# Power_Pos.net
KiCad netlist of a schematic drawn in Altium Designer
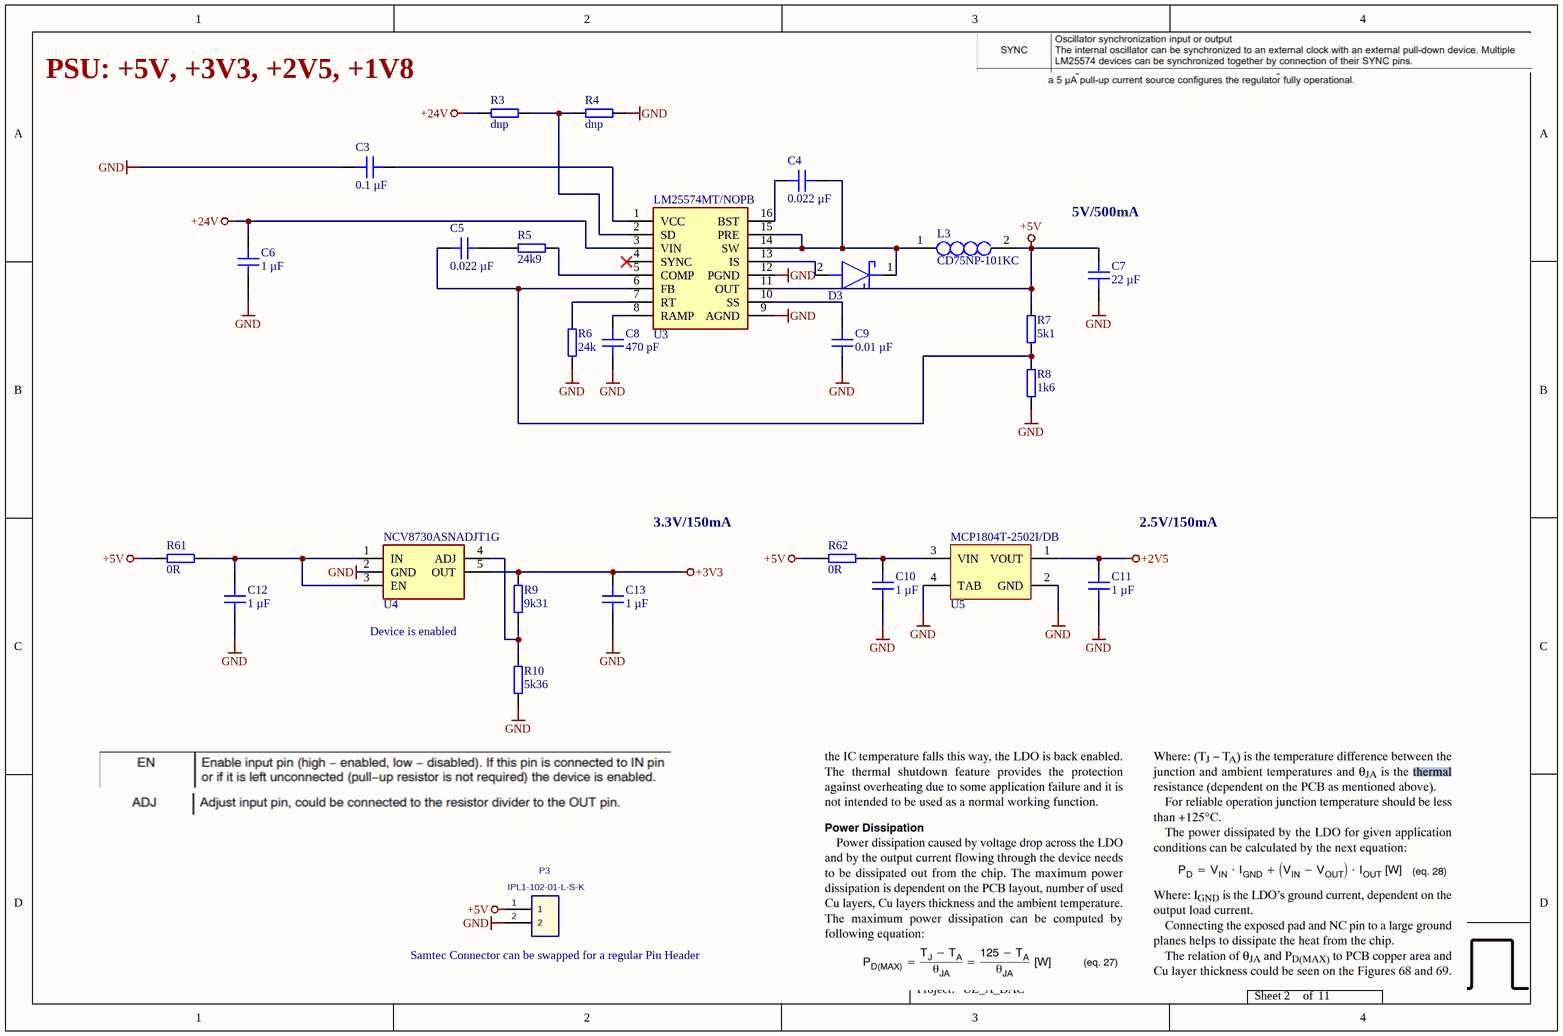
[diagram p0: Power_Pos.SchDoc]

(export (version "E")
  (design (tool "Eeschema 10.0.6"))
  (components
    (comp (ref "C3")
      (value "0.1 µF")
      (footprint "C_0603")
      (description "Capacitor 0603, 50 VDC, 0.1 µF, X7R")
      (fields
        (field (name "MANUFACTURER PART NUMBER") "C0603X104K5RAC7411")
        (field (name "MANUFACTURER") "KEMET")
        (field (name "CREATED FROM") "MGremer")
      )
      (libsource (lib "user") (part "Capacitor"))
    )
    (comp (ref "C4")
      (value "0.022 µF")
      (footprint "C_0805")
      (description "Capacitor 0805, 100 VDC, 0.022 µF, X7R")
      (fields
        (field (name "MANUFACTURER PART NUMBER") "C0805J223K1RACAUTO")
        (field (name "MANUFACTURER") "KEMET")
        (field (name "CREATED FROM") "MGremer")
      )
      (libsource (lib "user") (part "Capacitor"))
    )
    (comp (ref "C5")
      (value "0.022 µF")
      (footprint "C_0805")
      (description "Capacitor 0805, 100 VDC, 0.022 µF, X7R")
      (fields
        (field (name "MANUFACTURER PART NUMBER") "C0805J223K1RACAUTO")
        (field (name "MANUFACTURER") "KEMET")
        (field (name "CREATED FROM") "MGremer")
      )
      (libsource (lib "user") (part "Capacitor"))
    )
    (comp (ref "C6")
      (value "1 µF")
      (footprint "C_1206")
      (description "Capacitor 1206, 50 VDC, 1 µF, X7R")
      (fields
        (field (name "MANUFACTURER PART NUMBER") "C1206X105K5RECAUTO")
        (field (name "MANUFACTURER") "KEMET")
        (field (name "CREATED FROM") "MGremer")
      )
      (libsource (lib "user") (part "Capacitor"))
    )
    (comp (ref "C7")
      (value "22 µF")
      (footprint "C_0805")
      (description "Capacitor 0805, 25 VDC, 22 µF, X5R")
      (fields
        (field (name "MANUFACTURER PART NUMBER") "GRT21BR61E226ME13L")
        (field (name "MANUFACTURER") "muRata")
        (field (name "CREATED FROM") "MGremer")
      )
      (libsource (lib "user") (part "Capacitor"))
    )
    (comp (ref "C8")
      (value "470 pF")
      (footprint "C_0805")
      (description "Capacitor 0805, 50 VDC, 470 pF, X7R")
      (fields
        (field (name "MANUFACTURER PART NUMBER") "CC805KRX7R9BB471")
        (field (name "MANUFACTURER") "FH")
        (field (name "CREATED FROM") "MHlatky")
      )
      (libsource (lib "user") (part "Capacitor"))
    )
    (comp (ref "C9")
      (value "0.01 µF")
      (footprint "C_0603")
      (description "Capacitor 0603, 50 VDC, 0.01 µF, X7R")
      (fields
        (field (name "MANUFACTURER PART NUMBER") "GCJ188R71H103KA01D")
        (field (name "MANUFACTURER") "muRata")
        (field (name "CREATED FROM") "MGremer")
      )
      (libsource (lib "user") (part "Capacitor"))
    )
    (comp (ref "C10")
      (value "1 µF")
      (footprint "C_1206")
      (description "Capacitor 1206, 50 VDC, 1 µF, X7R")
      (fields
        (field (name "MANUFACTURER PART NUMBER") "C1206X105K5RECAUTO")
        (field (name "MANUFACTURER") "KEMET")
        (field (name "CREATED FROM") "MGremer")
      )
      (libsource (lib "user") (part "Capacitor"))
    )
    (comp (ref "C11")
      (value "1 µF")
      (footprint "C_1206")
      (description "Capacitor 1206, 50 VDC, 1 µF, X7R")
      (fields
        (field (name "MANUFACTURER PART NUMBER") "C1206X105K5RECAUTO")
        (field (name "MANUFACTURER") "KEMET")
        (field (name "CREATED FROM") "MGremer")
      )
      (libsource (lib "user") (part "Capacitor"))
    )
    (comp (ref "C12")
      (value "1 µF")
      (footprint "C_1206")
      (description "Capacitor 1206, 50 VDC, 1 µF, X7R")
      (fields
        (field (name "MANUFACTURER PART NUMBER") "C1206X105K5RECAUTO")
        (field (name "MANUFACTURER") "KEMET")
        (field (name "CREATED FROM") "MGremer")
      )
      (libsource (lib "user") (part "Capacitor"))
    )
    (comp (ref "C13")
      (value "1 µF")
      (footprint "C_1206")
      (description "Capacitor 1206, 50 VDC, 1 µF, X7R")
      (fields
        (field (name "MANUFACTURER PART NUMBER") "C1206X105K5RECAUTO")
        (field (name "MANUFACTURER") "KEMET")
        (field (name "CREATED FROM") "MGremer")
      )
      (libsource (lib "user") (part "Capacitor"))
    )
    (comp (ref "D3")
      (value "CDBA260-G")
      (footprint "DIOM5226X262N")
      (description "Schottky Diode, 60 V, 2 A")
      (fields
        (field (name "MANUFACTURER_PART_NUMBER") "CMSH2-60M TR13 PBFREE")
        (field (name "MANUFACTURER") "Central Semiconductor")
        (field (name "CREATED FROM") "MHlatky")
      )
      (libsource (lib "user") (part "CDBA260-G"))
    )
    (comp (ref "L3")
      (value "CD75NP-101KC")
      (footprint "784787121")
      (description "SMD Power Inductor, 100uH")
      (fields
        (field (name "MANUFACTURER_PART_NUMBER") "784787121")
        (field (name "MANUFACTURER") "Sumida")
        (field (name "CREATED FROM") "MHlatky")
      )
      (libsource (lib "user") (part "CD75NP-101KC"))
    )
    (comp (ref "P3")
      (value "IPL1-102-01-L-S-K")
      (footprint "IPL1-102-01-YYY-S-K")
      (description "2.54 mm Single Row Terminal Assembly")
      (fields (field (name "MANUFACTURER") "SAMTEC") (field (name "CREATED FROM") "MGremer"))
      (libsource (lib "user") (part "IPL1-102-XX-X-S-X"))
    )
    (comp (ref "R3")
      (value "dnp")
      (footprint "RES 0603_1608")
      (description "SMD resistor E24 series")
      (fields (field (name "CREATED FROM") "MGremer"))
      (libsource (lib "user") (part "Resistor"))
    )
    (comp (ref "R4")
      (value "dnp")
      (footprint "RES 0603_1608")
      (description "SMD resistor E24 series")
      (fields (field (name "CREATED FROM") "MGremer"))
      (libsource (lib "user") (part "Resistor"))
    )
    (comp (ref "R5")
      (value "24k9")
      (footprint "RES 0603_1608")
      (description "SMD resistor 1%")
      (fields
        (field (name "MANUFACTURER PART NUMBER") "CRCW060324K9FKEA")
        (field (name "MANUFACTURER") "Vishay")
        (field (name "CREATED FROM") "MGremer")
      )
      (libsource (lib "user") (part "Resistor"))
    )
    (comp (ref "R6")
      (value "24k")
      (footprint "RES 0603_1608")
      (description "SMD resistor E24 series")
      (fields
        (field (name "MANUFACTURER PART NUMBER") "RK73B1JTTD243J")
        (field (name "MANUFACTURER") "KOA Speer")
        (field (name "CREATED FROM") "MGremer")
      )
      (libsource (lib "user") (part "Resistor"))
    )
    (comp (ref "R7")
      (value "5k1")
      (footprint "RES 0603_1608")
      (description "SMD resistor E24 series")
      (fields
        (field (name "MANUFACTURER PART NUMBER") "RK73B1JTTDD512J")
        (field (name "MANUFACTURER") "KOA Speer")
        (field (name "CREATED FROM") "MGremer")
      )
      (libsource (lib "user") (part "Resistor"))
    )
    (comp (ref "R8")
      (value "1k6")
      (footprint "RES 0603_1608")
      (description "SMD resistor E24 series")
      (fields
        (field (name "MANUFACTURER PART NUMBER") "RK73B1JTTD162J")
        (field (name "MANUFACTURER") "KOA Speer")
        (field (name "CREATED FROM") "MGremer")
      )
      (libsource (lib "user") (part "Resistor"))
    )
    (comp (ref "R9")
      (value "9k31")
      (footprint "RES 0603_1608")
      (description "SMD resistor 1%")
      (fields
        (field (name "MANUFACTURER PART NUMBER") "ERJ3EKF9311V")
        (field (name "MANUFACTURER") "Panasonic")
        (field (name "CREATED FROM") "MGremer")
      )
      (libsource (lib "user") (part "Resistor"))
    )
    (comp (ref "R10")
      (value "5k36")
      (footprint "RES 0603_1608")
      (description "SMD resistor 1%")
      (fields
        (field (name "MANUFACTURER PART NUMBER") "AC0603FR-075K36L")
        (field (name "MANUFACTURER") "YAGEO")
        (field (name "CREATED FROM") "MGremer")
      )
      (libsource (lib "user") (part "Resistor"))
    )
    (comp (ref "R61")
      (value "0R")
      (footprint "RES 0603_1608")
      (description "SMD resistor E24 series")
      (fields
        (field (name "MANUFACTURER PART NUMBER") "RC0603JR-070RL")
        (field (name "MANUFACTURER") "YAGEO")
        (field (name "CREATED FROM") "MGremer")
      )
      (libsource (lib "user") (part "Resistor"))
    )
    (comp (ref "R62")
      (value "0R")
      (footprint "RES 0603_1608")
      (description "SMD resistor E24 series")
      (fields
        (field (name "MANUFACTURER PART NUMBER") "RC0603JR-070RL")
        (field (name "MANUFACTURER") "YAGEO")
        (field (name "CREATED FROM") "MGremer")
      )
      (libsource (lib "user") (part "Resistor"))
    )
    (comp (ref "U3")
      (value "LM25574MT/NOPB")
      (footprint "SOP65P640X120-16N")
      (description "42-V, 0.5-A Step-Down Switching Regulator")
      (fields (field (name "MANUFACTURER") "TI") (field (name "CREATED FROM") "MHlatky"))
      (libsource (lib "user") (part "LM25574MT_NOPB"))
    )
    (comp (ref "U4")
      (value "NCV8730ASNADJT1G")
      (footprint "SOT95P275X110-5N")
      (description "LDO Regulator, 150 mA, 38V, 1 A IQ, with PG")
      (fields (field (name "MANUFACTURER") "onsemi") (field (name "CREATED FROM") "MHlatky"))
      (libsource (lib "user") (part "NCV8730ASNADJT1G"))
    )
    (comp (ref "U5")
      (value "MCP1804T-2502I/DB")
      (footprint "SOT-223-DB3_N")
      (description "150 mA, 28V LDO Regulator With Shutdown")
      (fields (field (name "MANUFACTURER") "Microchip Technology") (field (name "CREATED FROM") "MHlatky"))
      (libsource (lib "user") (part "MCP1804T-2502I/DB"))
    )
  )
  (nets
    (net (code "1") (name "+2V5") (class "Default")
      (node (ref "C11") (pin "2") (pinfunction "2_2") (pintype "passive"))
      (node (ref "U5") (pin "1") (pinfunction "VOUT_1") (pintype "power_in"))
    )
    (net (code "2") (name "+3V3") (class "Default")
      (node (ref "C13") (pin "2") (pinfunction "2_2") (pintype "passive"))
      (node (ref "R9") (pin "2") (pinfunction "2_2") (pintype "passive"))
      (node (ref "U4") (pin "5") (pinfunction "OUT_5") (pintype "passive"))
    )
    (net (code "3") (name "+5V") (class "Default")
      (node (ref "C7") (pin "2") (pinfunction "2_2") (pintype "passive"))
      (node (ref "L3") (pin "2") (pinfunction "2_2") (pintype "passive"))
      (node (ref "P3") (pin "1") (pinfunction "1_1") (pintype "passive"))
      (node (ref "R61") (pin "1") (pinfunction "1_1") (pintype "passive"))
      (node (ref "R62") (pin "1") (pinfunction "1_1") (pintype "passive"))
      (node (ref "R7") (pin "2") (pinfunction "2_2") (pintype "passive"))
      (node (ref "U3") (pin "11") (pinfunction "OUT_11") (pintype "passive"))
    )
    (net (code "4") (name "+24V") (class "Default")
      (node (ref "C6") (pin "2") (pinfunction "2_2") (pintype "passive"))
      (node (ref "R3") (pin "1") (pinfunction "1_1") (pintype "passive"))
      (node (ref "U3") (pin "3") (pinfunction "VIN_3") (pintype "passive"))
    )
    (net (code "5") (name "GND") (class "Default")
      (node (ref "C10") (pin "1") (pinfunction "1_1") (pintype "passive"))
      (node (ref "C11") (pin "1") (pinfunction "1_1") (pintype "passive"))
      (node (ref "C12") (pin "1") (pinfunction "1_1") (pintype "passive"))
      (node (ref "C13") (pin "1") (pinfunction "1_1") (pintype "passive"))
      (node (ref "C3") (pin "2") (pinfunction "2_2") (pintype "passive"))
      (node (ref "C6") (pin "1") (pinfunction "1_1") (pintype "passive"))
      (node (ref "C7") (pin "1") (pinfunction "1_1") (pintype "passive"))
      (node (ref "C8") (pin "1") (pinfunction "1_1") (pintype "passive"))
      (node (ref "C9") (pin "1") (pinfunction "1_1") (pintype "passive"))
      (node (ref "P3") (pin "2") (pinfunction "2_2") (pintype "passive"))
      (node (ref "R10") (pin "1") (pinfunction "1_1") (pintype "passive"))
      (node (ref "R4") (pin "2") (pinfunction "2_2") (pintype "passive"))
      (node (ref "R6") (pin "1") (pinfunction "1_1") (pintype "passive"))
      (node (ref "R8") (pin "1") (pinfunction "1_1") (pintype "passive"))
      (node (ref "U3") (pin "12") (pinfunction "PGND_12") (pintype "passive"))
      (node (ref "U3") (pin "9") (pinfunction "AGND_9") (pintype "passive"))
      (node (ref "U4") (pin "2") (pinfunction "GND_2") (pintype "passive"))
      (node (ref "U5") (pin "2") (pinfunction "GND_2") (pintype "power_in"))
      (node (ref "U5") (pin "4") (pinfunction "TAB_4") (pintype "power_in"))
    )
    (net (code "6") (name "Net-(C5-Pad2)") (class "Default")
      (node (ref "C5") (pin "2") (pinfunction "2_2") (pintype "passive"))
      (node (ref "R5") (pin "1") (pinfunction "1_1") (pintype "passive"))
    )
    (net (code "7") (name "Net-(D3-A)") (class "Default")
      (node (ref "D3") (pin "2") (pinfunction "A_2") (pintype "passive"))
      (node (ref "U3") (pin "13") (pinfunction "IS_13") (pintype "passive"))
    )
    (net (code "8") (name "Net-(D3-K)") (class "Default")
      (node (ref "C4") (pin "2") (pinfunction "2_2") (pintype "passive"))
      (node (ref "D3") (pin "1") (pinfunction "K_1") (pintype "passive"))
      (node (ref "L3") (pin "1") (pinfunction "1_1") (pintype "passive"))
      (node (ref "U3") (pin "14") (pinfunction "SW_14") (pintype "passive"))
      (node (ref "U3") (pin "15") (pinfunction "PRE_15") (pintype "passive"))
    )
    (net (code "9") (name "Net-(U3-BST)") (class "Default")
      (node (ref "C4") (pin "1") (pinfunction "1_1") (pintype "passive"))
      (node (ref "U3") (pin "16") (pinfunction "BST_16") (pintype "passive"))
    )
    (net (code "10") (name "Net-(U3-COMP)") (class "Default")
      (node (ref "R5") (pin "2") (pinfunction "2_2") (pintype "passive"))
      (node (ref "U3") (pin "5") (pinfunction "COMP_5") (pintype "passive"))
    )
    (net (code "11") (name "Net-(U3-FB)") (class "Default")
      (node (ref "C5") (pin "1") (pinfunction "1_1") (pintype "passive"))
      (node (ref "R7") (pin "1") (pinfunction "1_1") (pintype "passive"))
      (node (ref "R8") (pin "2") (pinfunction "2_2") (pintype "passive"))
      (node (ref "U3") (pin "6") (pinfunction "FB_6") (pintype "passive"))
    )
    (net (code "12") (name "Net-(U3-RAMP)") (class "Default")
      (node (ref "C8") (pin "2") (pinfunction "2_2") (pintype "passive"))
      (node (ref "U3") (pin "8") (pinfunction "RAMP_8") (pintype "passive"))
    )
    (net (code "13") (name "Net-(U3-RT)") (class "Default")
      (node (ref "R6") (pin "2") (pinfunction "2_2") (pintype "passive"))
      (node (ref "U3") (pin "7") (pinfunction "RT_7") (pintype "passive"))
    )
    (net (code "14") (name "Net-(U3-SD)") (class "Default")
      (node (ref "R3") (pin "2") (pinfunction "2_2") (pintype "passive"))
      (node (ref "R4") (pin "1") (pinfunction "1_1") (pintype "passive"))
      (node (ref "U3") (pin "2") (pinfunction "SD_2") (pintype "passive"))
    )
    (net (code "15") (name "Net-(U3-SS)") (class "Default")
      (node (ref "C9") (pin "2") (pinfunction "2_2") (pintype "passive"))
      (node (ref "U3") (pin "10") (pinfunction "SS_10") (pintype "passive"))
    )
    (net (code "16") (name "Net-(U3-VCC)") (class "Default")
      (node (ref "C3") (pin "1") (pinfunction "1_1") (pintype "passive"))
      (node (ref "U3") (pin "1") (pinfunction "VCC_1") (pintype "passive"))
    )
    (net (code "17") (name "Net-(U4-ADJ)") (class "Default")
      (node (ref "R10") (pin "2") (pinfunction "2_2") (pintype "passive"))
      (node (ref "R9") (pin "1") (pinfunction "1_1") (pintype "passive"))
      (node (ref "U4") (pin "4") (pinfunction "ADJ_4") (pintype "passive"))
    )
    (net (code "18") (name "Net-(U4-EN)") (class "Default")
      (node (ref "C12") (pin "2") (pinfunction "2_2") (pintype "passive"))
      (node (ref "R61") (pin "2") (pinfunction "2_2") (pintype "passive"))
      (node (ref "U4") (pin "1") (pinfunction "IN_1") (pintype "passive"))
      (node (ref "U4") (pin "3") (pinfunction "EN_3") (pintype "passive"))
    )
    (net (code "19") (name "Net-(U5-VIN)") (class "Default")
      (node (ref "C10") (pin "2") (pinfunction "2_2") (pintype "passive"))
      (node (ref "R62") (pin "2") (pinfunction "2_2") (pintype "passive"))
      (node (ref "U5") (pin "3") (pinfunction "VIN_3") (pintype "power_in"))
    )
    (net (code "20") (name "unconnected-(U3-SYNC-Pad4)") (class "Default")
      (node (ref "U3") (pin "4") (pinfunction "SYNC_4") (pintype "passive+no_connect"))
    )
  )
)
